# Fri3D_2018_01.net
KiCad netlist of a schematic drawn in Altium Designer
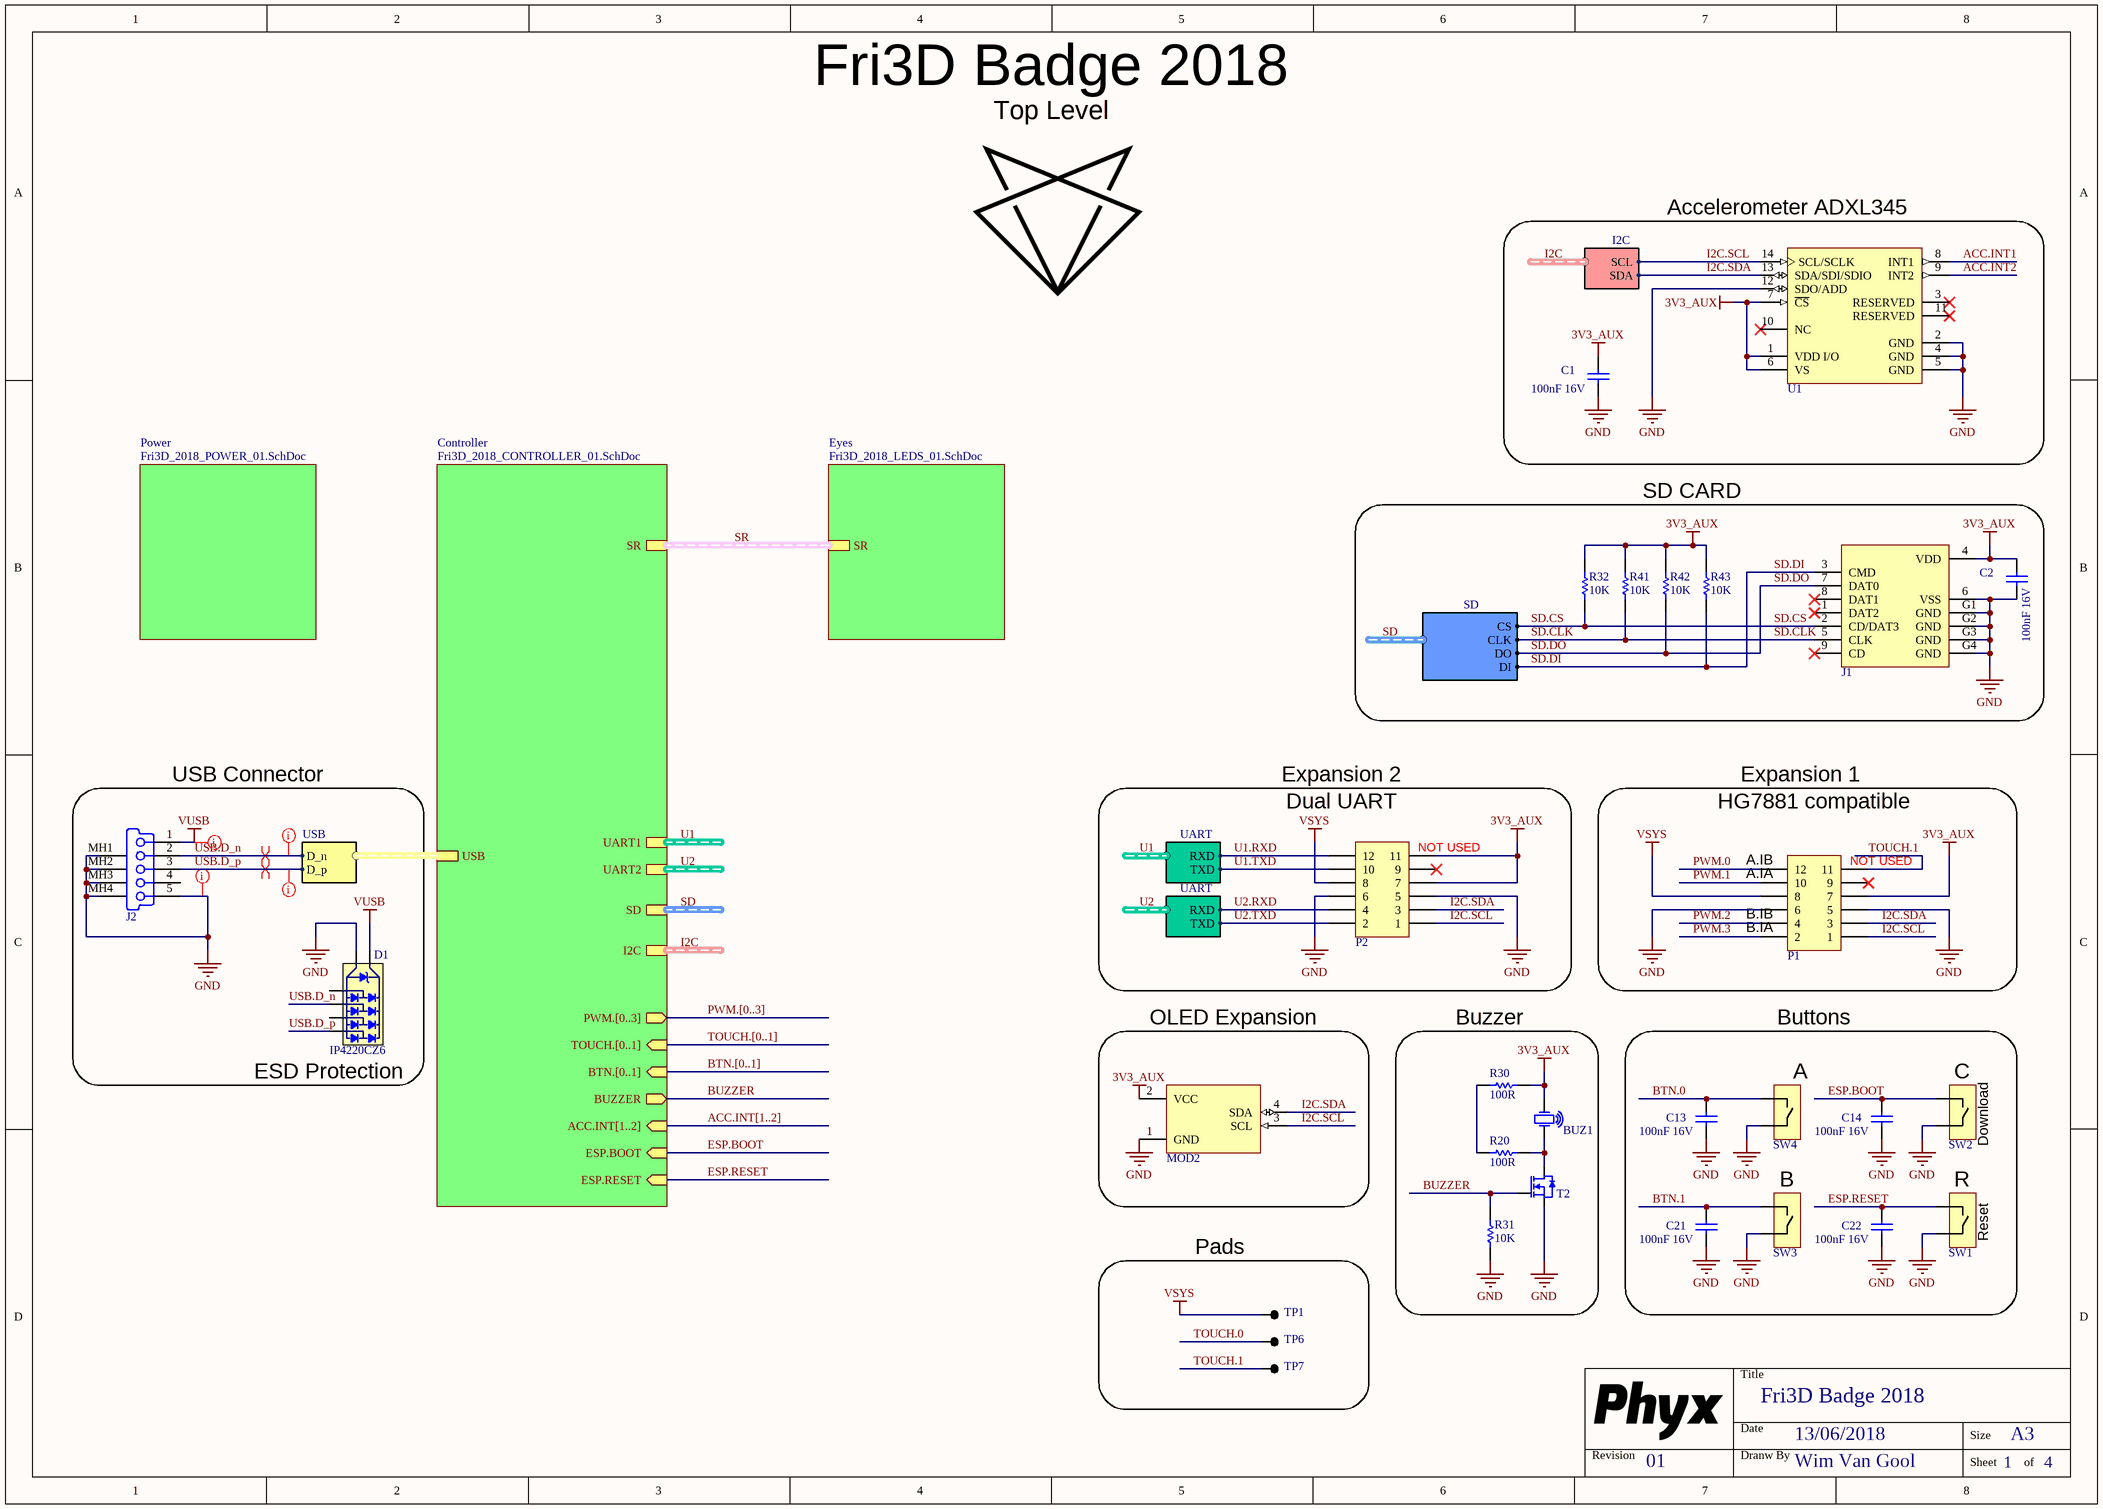
[diagram p0: Fri3D_2018_01.SchDoc]

(export (version "E")
  (design (tool "Eeschema 10.0.6"))
  (components
    (comp (ref "BUZ1")
      (value "12x12x3mm Piezo Buzzer Transducer 81dB")
      (footprint "CUI_CMT-1203-SMT")
      (description "Crystal Oscillator")
      (libsource (lib "Phyx_Components") (part "Buzzer"))
    )
    (comp (ref "C1")
      (value "100nF 16V")
      (footprint "C0603_N")
      (description "Capacitor Ceramic")
      (libsource (lib "Phyx_Components") (part "CAP_CERAMIC"))
    )
    (comp (ref "C2")
      (value "100nF 16V")
      (footprint "C0603_N")
      (description "Capacitor Ceramic")
      (libsource (lib "Phyx_Components") (part "CAP_CERAMIC"))
    )
    (comp (ref "C13")
      (value "100nF 16V")
      (footprint "C0603_N")
      (description "Capacitor Ceramic")
      (libsource (lib "Phyx_Components") (part "CAP_CERAMIC"))
    )
    (comp (ref "C14")
      (value "100nF 16V")
      (footprint "C0603_N")
      (description "Capacitor Ceramic")
      (libsource (lib "Phyx_Components") (part "CAP_CERAMIC"))
    )
    (comp (ref "C21")
      (value "100nF 16V")
      (footprint "C0603_N")
      (description "Capacitor Ceramic")
      (libsource (lib "Phyx_Components") (part "CAP_CERAMIC"))
    )
    (comp (ref "C22")
      (value "100nF 16V")
      (footprint "C0603_N")
      (description "Capacitor Ceramic")
      (libsource (lib "Phyx_Components") (part "CAP_CERAMIC"))
    )
    (comp (ref "D1")
      (value "IP4220CZ6")
      (footprint "NXP_SOT457")
      (description "=Description")
      (fields (field (name "Comment") "TVS Diode Dual USB"))
      (libsource (lib "Phyx_Components") (part "NXP_IP4220CZ6"))
    )
    (comp (ref "J1")
      (value "Micro SD PiPo Push-Push")
      (footprint "TFP09-2-12B")
      (description "=Description")
      (libsource (lib "Phyx_Components") (part "TFP09-2-12B"))
    )
    (comp (ref "J2")
      (value "Amphenol FCI 10118194-0001LF Micro USB 1.8A TH Lock")
      (footprint "FCI_10118194-0001LF")
      (libsource (lib "Phyx_Components") (part "USB_OTG_Mini-B"))
    )
    (comp (ref "MOD2")
      (value "SSD1306 based 128x64 OLED, I2C, module")
      (footprint "OLED_MOD_0.96_I2C")
      (libsource (lib "Phyx_Components") (part "OLED_MOD_0.96_I2C"))
    )
    (comp (ref "P1")
      (value "Receptacle 6x2 SMD low profile")
      (footprint "WE_610312243021_POST")
      (libsource (lib "Phyx_Components") (part "Header 6X2"))
    )
    (comp (ref "P2")
      (value "Receptacle 6x2 SMD low profile")
      (footprint "WE_610312243021_POST")
      (libsource (lib "Phyx_Components") (part "Header 6X2"))
    )
    (comp (ref "R20")
      (value "100R")
      (footprint "R0603_N")
      (fields (field (name "Comment") "RESISTOR"))
      (libsource (lib "Phyx_Components") (part "RESISTOR"))
    )
    (comp (ref "R30")
      (value "100R")
      (footprint "R0603_N")
      (fields (field (name "Comment") "RESISTOR"))
      (libsource (lib "Phyx_Components") (part "RESISTOR"))
    )
    (comp (ref "R31")
      (value "10K")
      (footprint "R0603_N")
      (fields (field (name "Comment") "RESISTOR"))
      (libsource (lib "Phyx_Components") (part "RESISTOR"))
    )
    (comp (ref "R32")
      (value "10K")
      (footprint "R0603_N")
      (fields (field (name "Comment") "RESISTOR"))
      (libsource (lib "Phyx_Components") (part "RESISTOR"))
    )
    (comp (ref "R41")
      (value "10K")
      (footprint "R0603_N")
      (fields (field (name "Comment") "RESISTOR"))
      (libsource (lib "Phyx_Components") (part "RESISTOR"))
    )
    (comp (ref "R42")
      (value "10K")
      (footprint "R0603_N")
      (fields (field (name "Comment") "RESISTOR"))
      (libsource (lib "Phyx_Components") (part "RESISTOR"))
    )
    (comp (ref "R43")
      (value "10K")
      (footprint "R0603_N")
      (fields (field (name "Comment") "RESISTOR"))
      (libsource (lib "Phyx_Components") (part "RESISTOR"))
    )
    (comp (ref "SW1")
      (value "4.5x4.5mm tact SMD H3,8mm")
      (footprint "WE_430181038816")
      (libsource (lib "Phyx_Components") (part "SW_TACT"))
    )
    (comp (ref "SW2")
      (value "4.5x4.5mm tact SMD H3,8mm")
      (footprint "WE_430181038816")
      (libsource (lib "Phyx_Components") (part "SW_TACT"))
    )
    (comp (ref "SW3")
      (value "4.5x4.5mm tact SMD H3,8mm")
      (footprint "WE_430181038816")
      (libsource (lib "Phyx_Components") (part "SW_TACT"))
    )
    (comp (ref "SW4")
      (value "4.5x4.5mm tact SMD H3,8mm")
      (footprint "WE_430181038816")
      (libsource (lib "Phyx_Components") (part "SW_TACT"))
    )
    (comp (ref "T2")
      (value "0.2A N-Ch MOSFET Vgs 3.2")
      (footprint "SOT23-3")
      (libsource (lib "Phyx_Components") (part "N_MOSFET_GSD"))
    )
    (comp (ref "TP1")
      (value "TEST_PAD")
      (footprint "TP_0.8mm")
      (libsource (lib "Phyx_Components") (part "TEST_PAD"))
    )
    (comp (ref "TP6")
      (value "TEST_PAD")
      (footprint "TP_0.8mm")
      (libsource (lib "Phyx_Components") (part "TEST_PAD"))
    )
    (comp (ref "TP7")
      (value "TEST_PAD")
      (footprint "TP_0.8mm")
      (libsource (lib "Phyx_Components") (part "TEST_PAD"))
    )
    (comp (ref "U1")
      (value "3-Axis, ±2 g/±4 g/±8 g/±16 g Digital Accelerometer")
      (footprint "AD_CC-14-1")
      (description "=Description")
      (libsource (lib "Phyx_Components") (part "ADXL345"))
    )
  )
  (nets
    (net (code "11") (name "/ACC.INT1") (class "Default")
      (node (ref "U1") (pin "8") (pinfunction "INT1_8") (pintype "output"))
    )
    (net (code "12") (name "/ACC.INT2") (class "Default")
      (node (ref "U1") (pin "9") (pinfunction "INT2_9") (pintype "output"))
    )
    (net (code "14") (name "/BTN.0") (class "Default")
      (node (ref "C13") (pin "1") (pinfunction "1_1") (pintype "passive"))
      (node (ref "SW4") (pin "1") (pinfunction "1_1") (pintype "passive"))
    )
    (net (code "15") (name "/BTN.1") (class "Default")
      (node (ref "C21") (pin "1") (pinfunction "1_1") (pintype "passive"))
      (node (ref "SW3") (pin "1") (pinfunction "1_1") (pintype "passive"))
    )
    (net (code "17") (name "/BUZZER") (class "Default")
      (node (ref "R31") (pin "1") (pinfunction "1_1") (pintype "passive"))
      (node (ref "T2") (pin "1") (pinfunction "G_1") (pintype "passive"))
    )
    (net (code "18") (name "/ESP.BOOT") (class "Default")
      (node (ref "C14") (pin "1") (pinfunction "1_1") (pintype "passive"))
      (node (ref "SW2") (pin "1") (pinfunction "1_1") (pintype "passive"))
    )
    (net (code "19") (name "/ESP.RESET") (class "Default")
      (node (ref "C22") (pin "1") (pinfunction "1_1") (pintype "passive"))
      (node (ref "SW1") (pin "1") (pinfunction "1_1") (pintype "passive"))
    )
    (net (code "20") (name "/I2C.SCL") (class "Default")
      (node (ref "MOD2") (pin "3") (pinfunction "SCL_3") (pintype "input"))
      (node (ref "P1") (pin "1") (pinfunction "1_1") (pintype "passive"))
      (node (ref "P2") (pin "1") (pinfunction "1_1") (pintype "passive"))
      (node (ref "U1") (pin "14") (pinfunction "SCL/SCLK_14") (pintype "input"))
    )
    (net (code "21") (name "/I2C.SDA") (class "Default")
      (node (ref "MOD2") (pin "4") (pinfunction "SDA_4") (pintype "bidirectional"))
      (node (ref "P1") (pin "3") (pinfunction "3_3") (pintype "passive"))
      (node (ref "P2") (pin "3") (pinfunction "3_3") (pintype "passive"))
      (node (ref "U1") (pin "13") (pinfunction "SDA/SDI/SDIO_13") (pintype "bidirectional"))
    )
    (net (code "23") (name "/PWM.0") (class "Default")
      (node (ref "P1") (pin "12") (pinfunction "12_12") (pintype "passive"))
    )
    (net (code "24") (name "/PWM.1") (class "Default")
      (node (ref "P1") (pin "10") (pinfunction "10_10") (pintype "passive"))
    )
    (net (code "25") (name "/PWM.2") (class "Default")
      (node (ref "P1") (pin "4") (pinfunction "4_4") (pintype "passive"))
    )
    (net (code "26") (name "/PWM.3") (class "Default")
      (node (ref "P1") (pin "2") (pinfunction "2_2") (pintype "passive"))
    )
    (net (code "28") (name "/SD.CLK") (class "Default")
      (node (ref "J1") (pin "5") (pinfunction "CLK_5") (pintype "passive"))
      (node (ref "R41") (pin "2") (pinfunction "2_2") (pintype "passive"))
    )
    (net (code "29") (name "/SD.CS") (class "Default")
      (node (ref "J1") (pin "2") (pinfunction "CD/DAT3_2") (pintype "passive"))
      (node (ref "R32") (pin "2") (pinfunction "2_2") (pintype "passive"))
    )
    (net (code "30") (name "/SD.DI") (class "Default")
      (node (ref "J1") (pin "3") (pinfunction "CMD_3") (pintype "passive"))
      (node (ref "R43") (pin "2") (pinfunction "2_2") (pintype "passive"))
    )
    (net (code "31") (name "/SD.DO") (class "Default")
      (node (ref "J1") (pin "7") (pinfunction "DAT0_7") (pintype "passive"))
      (node (ref "R42") (pin "2") (pinfunction "2_2") (pintype "passive"))
    )
    (net (code "33") (name "/TOUCH.0") (class "Default")
      (node (ref "TP6") (pin "1") (pinfunction "1_1") (pintype "passive"))
    )
    (net (code "34") (name "/TOUCH.1") (class "Default")
      (node (ref "P1") (pin "11") (pinfunction "11_11") (pintype "passive"))
      (node (ref "TP7") (pin "1") (pinfunction "1_1") (pintype "passive"))
    )
    (net (code "36") (name "/U1.RXD") (class "Default")
      (node (ref "P2") (pin "12") (pinfunction "12_12") (pintype "passive"))
    )
    (net (code "37") (name "/U1.TXD") (class "Default")
      (node (ref "P2") (pin "10") (pinfunction "10_10") (pintype "passive"))
    )
    (net (code "39") (name "/U2.RXD") (class "Default")
      (node (ref "P2") (pin "4") (pinfunction "4_4") (pintype "passive"))
    )
    (net (code "40") (name "/U2.TXD") (class "Default")
      (node (ref "P2") (pin "2") (pinfunction "2_2") (pintype "passive"))
    )
    (net (code "42") (name "/USB.D_n") (class "Default")
      (node (ref "D1") (pin "1") (pinfunction "1_1") (pintype "passive"))
      (node (ref "J2") (pin "2") (pinfunction "D-_2") (pintype "passive"))
    )
    (net (code "43") (name "/USB.D_p") (class "Default")
      (node (ref "D1") (pin "6") (pinfunction "6_6") (pintype "passive"))
      (node (ref "J2") (pin "3") (pinfunction "D+_3") (pintype "passive"))
    )
    (net (code "50") (name "3V3_AUX") (class "Default")
      (node (ref "BUZ1") (pin "1") (pinfunction "OSC1_1") (pintype "passive"))
      (node (ref "C1") (pin "1") (pinfunction "1_1") (pintype "passive"))
      (node (ref "C2") (pin "1") (pinfunction "1_1") (pintype "passive"))
      (node (ref "J1") (pin "4") (pinfunction "VDD_4") (pintype "power_in"))
      (node (ref "MOD2") (pin "2") (pinfunction "VCC_2") (pintype "power_in"))
      (node (ref "P1") (pin "7") (pinfunction "7_7") (pintype "passive"))
      (node (ref "P2") (pin "11") (pinfunction "11_11") (pintype "passive"))
      (node (ref "P2") (pin "7") (pinfunction "7_7") (pintype "passive"))
      (node (ref "R30") (pin "1") (pinfunction "1_1") (pintype "passive"))
      (node (ref "R32") (pin "1") (pinfunction "1_1") (pintype "passive"))
      (node (ref "R41") (pin "1") (pinfunction "1_1") (pintype "passive"))
      (node (ref "R42") (pin "1") (pinfunction "1_1") (pintype "passive"))
      (node (ref "R43") (pin "1") (pinfunction "1_1") (pintype "passive"))
      (node (ref "U1") (pin "1") (pinfunction "VDD_I/O_1") (pintype "power_in"))
      (node (ref "U1") (pin "6") (pinfunction "VS_6") (pintype "power_in"))
      (node (ref "U1") (pin "7") (pinfunction "~{CS}_7") (pintype "input"))
    )
    (net (code "51") (name "GND") (class "Default")
      (node (ref "C1") (pin "2") (pinfunction "2_2") (pintype "passive"))
      (node (ref "C13") (pin "2") (pinfunction "2_2") (pintype "passive"))
      (node (ref "C14") (pin "2") (pinfunction "2_2") (pintype "passive"))
      (node (ref "C2") (pin "2") (pinfunction "2_2") (pintype "passive"))
      (node (ref "C21") (pin "2") (pinfunction "2_2") (pintype "passive"))
      (node (ref "C22") (pin "2") (pinfunction "2_2") (pintype "passive"))
      (node (ref "D1") (pin "2") (pinfunction "GND_2") (pintype "passive"))
      (node (ref "J1") (pin "6") (pinfunction "VSS_6") (pintype "power_in"))
      (node (ref "J1") (pin "G1") (pinfunction "GND_G1") (pintype "power_in"))
      (node (ref "J1") (pin "G2") (pinfunction "GND_G2") (pintype "power_in"))
      (node (ref "J1") (pin "G3") (pinfunction "GND_G3") (pintype "power_in"))
      (node (ref "J1") (pin "G4") (pinfunction "GND_G4") (pintype "power_in"))
      (node (ref "J2") (pin "5") (pinfunction "GND_5") (pintype "passive"))
      (node (ref "J2") (pin "MH1") (pinfunction "Tab_MH1") (pintype "passive"))
      (node (ref "J2") (pin "MH2") (pinfunction "Tab_MH2") (pintype "passive"))
      (node (ref "J2") (pin "MH3") (pinfunction "Tab_MH3") (pintype "passive"))
      (node (ref "J2") (pin "MH4") (pinfunction "Tab_MH4") (pintype "passive"))
      (node (ref "MOD2") (pin "1") (pinfunction "GND_1") (pintype "power_in"))
      (node (ref "P1") (pin "5") (pinfunction "5_5") (pintype "passive"))
      (node (ref "P1") (pin "6") (pinfunction "6_6") (pintype "passive"))
      (node (ref "P2") (pin "5") (pinfunction "5_5") (pintype "passive"))
      (node (ref "P2") (pin "6") (pinfunction "6_6") (pintype "passive"))
      (node (ref "R31") (pin "2") (pinfunction "2_2") (pintype "passive"))
      (node (ref "SW1") (pin "2") (pinfunction "2_2") (pintype "passive"))
      (node (ref "SW2") (pin "2") (pinfunction "2_2") (pintype "passive"))
      (node (ref "SW3") (pin "2") (pinfunction "2_2") (pintype "passive"))
      (node (ref "SW4") (pin "2") (pinfunction "2_2") (pintype "passive"))
      (node (ref "T2") (pin "2") (pinfunction "S_2") (pintype "passive"))
      (node (ref "U1") (pin "12") (pinfunction "SDO/ADD_12") (pintype "bidirectional"))
      (node (ref "U1") (pin "2") (pinfunction "GND_2") (pintype "power_in"))
      (node (ref "U1") (pin "4") (pinfunction "GND_4") (pintype "power_in"))
      (node (ref "U1") (pin "5") (pinfunction "GND_5") (pintype "power_in"))
    )
    (net (code "52") (name "Net-(BUZ1-OSC2)") (class "Default")
      (node (ref "BUZ1") (pin "2") (pinfunction "OSC2_2") (pintype "passive"))
      (node (ref "R20") (pin "1") (pinfunction "1_1") (pintype "passive"))
      (node (ref "T2") (pin "3") (pinfunction "D_3") (pintype "passive"))
    )
    (net (code "53") (name "Net-(R20-Pad2)") (class "Default")
      (node (ref "R20") (pin "2") (pinfunction "2_2") (pintype "passive"))
      (node (ref "R30") (pin "2") (pinfunction "2_2") (pintype "passive"))
    )
    (net (code "54") (name "VSYS") (class "Default")
      (node (ref "P1") (pin "8") (pinfunction "8_8") (pintype "passive"))
      (node (ref "P2") (pin "8") (pinfunction "8_8") (pintype "passive"))
      (node (ref "TP1") (pin "1") (pinfunction "1_1") (pintype "passive"))
    )
    (net (code "55") (name "VUSB") (class "Default")
      (node (ref "D1") (pin "5") (pinfunction "VBus_5") (pintype "passive"))
      (node (ref "J2") (pin "1") (pinfunction "V_BUS_(5V)_1") (pintype "passive"))
    )
    (net (code "56") (name "unconnected-(D1-Pad3)") (class "Default")
      (node (ref "D1") (pin "3") (pinfunction "3_3") (pintype "passive"))
    )
    (net (code "57") (name "unconnected-(D1-Pad4)") (class "Default")
      (node (ref "D1") (pin "4") (pinfunction "4_4") (pintype "passive"))
    )
    (net (code "58") (name "unconnected-(J1-CD-Pad9)") (class "Default")
      (node (ref "J1") (pin "9") (pinfunction "CD_9") (pintype "passive+no_connect"))
    )
    (net (code "59") (name "unconnected-(J1-DAT1-Pad8)") (class "Default")
      (node (ref "J1") (pin "8") (pinfunction "DAT1_8") (pintype "passive+no_connect"))
    )
    (net (code "60") (name "unconnected-(J1-DAT2-Pad1)") (class "Default")
      (node (ref "J1") (pin "1") (pinfunction "DAT2_1") (pintype "passive+no_connect"))
    )
    (net (code "61") (name "unconnected-(J2-NC-Pad4)") (class "Default")
      (node (ref "J2") (pin "4") (pinfunction "NC_4") (pintype "passive"))
    )
    (net (code "62") (name "unconnected-(P1-Pad9)") (class "Default")
      (node (ref "P1") (pin "9") (pinfunction "9_9") (pintype "passive+no_connect"))
    )
    (net (code "63") (name "unconnected-(P2-Pad9)") (class "Default")
      (node (ref "P2") (pin "9") (pinfunction "9_9") (pintype "passive+no_connect"))
    )
    (net (code "64") (name "unconnected-(U1-NC-Pad10)") (class "Default")
      (node (ref "U1") (pin "10") (pinfunction "NC_10") (pintype "passive+no_connect"))
    )
    (net (code "65") (name "unconnected-(U1-RESERVED-Pad3)") (class "Default")
      (node (ref "U1") (pin "3") (pinfunction "RESERVED_3") (pintype "passive+no_connect"))
    )
    (net (code "66") (name "unconnected-(U1-RESERVED-Pad11)") (class "Default")
      (node (ref "U1") (pin "11") (pinfunction "RESERVED_11") (pintype "passive+no_connect"))
    )
  )
)
